# Flasher_2Ch_Astable.net
KiCad netlist of a schematic drawn in Altium Designer
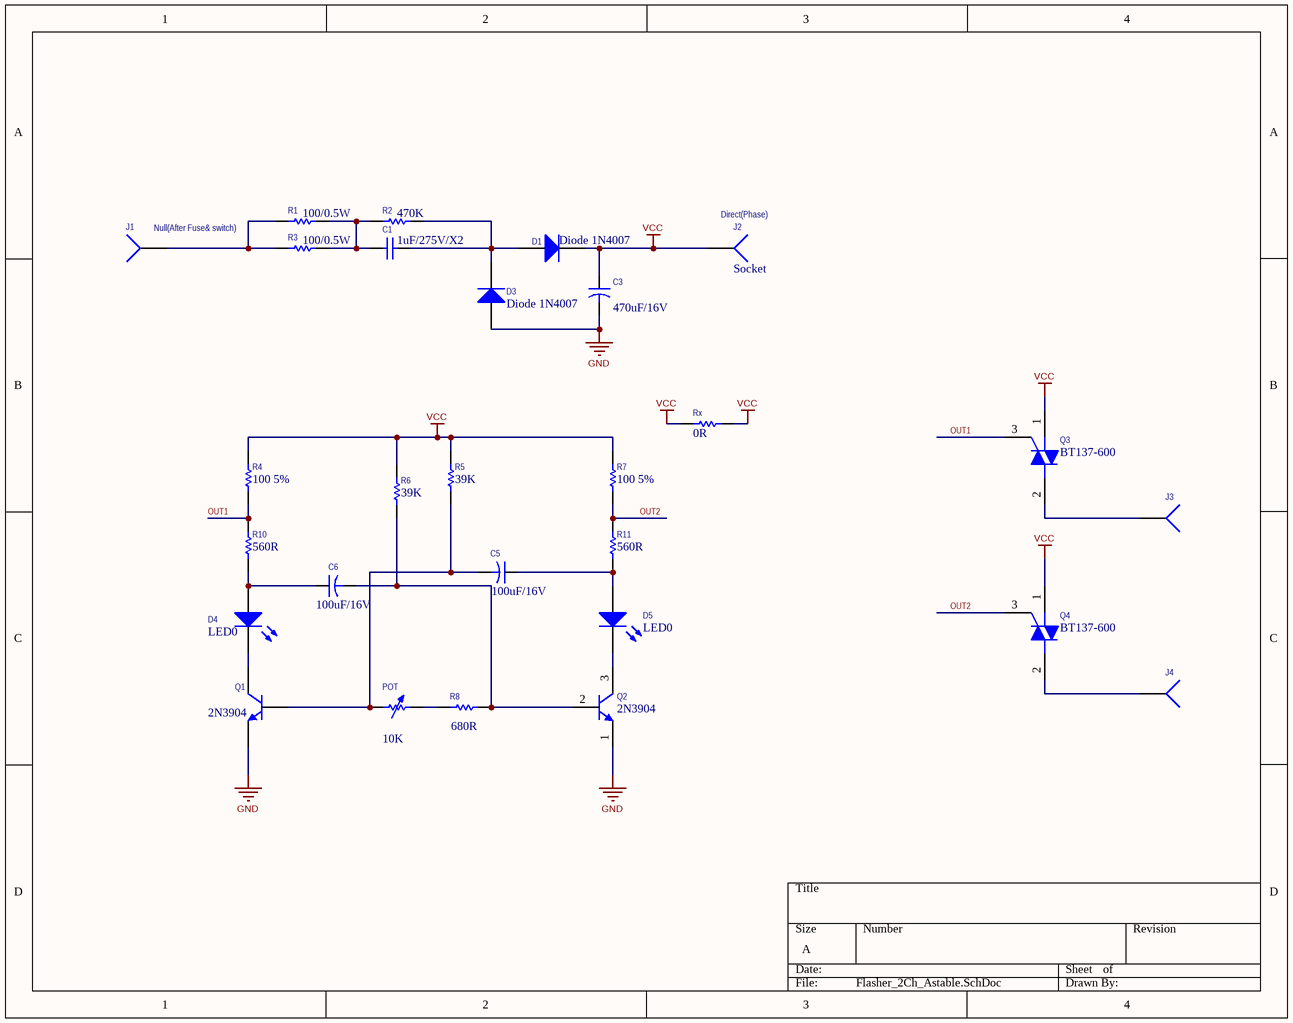
[diagram p0: Flasher_2Ch_Astable.SchDoc]

(export (version "E")
  (design (tool "Eeschema 10.0.6"))
  (components
    (comp (ref "C1")
      (value "1uF/275V/X2")
      (footprint "Cap_polyester_275V_P22.5")
      (description "Capacitor")
      (fields (field (name "Comment") "Cap") (field (name "PUBLISHER") "Altium Limited"))
      (libsource (lib "Miscellaneous Devices") (part "Cap"))
    )
    (comp (ref "C3")
      (value "470uF/16V")
      (footprint "Cap electrolitic radial 8x12-3.5")
      (description "Capacitor")
      (fields (field (name "Comment") "Cap2") (field (name "PUBLISHER") "Altium Limited"))
      (libsource (lib "Miscellaneous Devices") (part "Cap2"))
    )
    (comp (ref "C5")
      (value "100uF/16V")
      (footprint "Cap electrolitic radial 5x11-2")
      (description "Capacitor")
      (fields (field (name "Comment") "Cap2") (field (name "PUBLISHER") "Altium Limited"))
      (libsource (lib "Miscellaneous Devices") (part "Cap2"))
    )
    (comp (ref "C6")
      (value "100uF/16V")
      (footprint "Cap electrolitic radial 5x11-2")
      (description "Capacitor")
      (fields (field (name "Comment") "Cap2") (field (name "PUBLISHER") "Altium Limited"))
      (libsource (lib "Miscellaneous Devices") (part "Cap2"))
    )
    (comp (ref "D1")
      (value "Diode 1N4007")
      (footprint "DO-204AL")
      (description "1 Amp General Purpose Rectifier")
      (fields (field (name "PUBLISHER") "Altium Limited"))
      (libsource (lib "Miscellaneous Devices") (part "Diode 1N4007"))
    )
    (comp (ref "D3")
      (value "Diode 1N4007")
      (footprint "DO-204AL")
      (description "1 Amp General Purpose Rectifier")
      (fields (field (name "PUBLISHER") "Altium Limited"))
      (libsource (lib "Miscellaneous Devices") (part "Diode 1N4007"))
    )
    (comp (ref "D4")
      (value "LED0")
      (footprint "LED5MM_RED")
      (description "Typical INFRARED GaAs LED")
      (fields (field (name "PUBLISHER") "Altium Limited"))
      (libsource (lib "Miscellaneous Devices") (part "LED0"))
    )
    (comp (ref "D5")
      (value "LED0")
      (footprint "LED5MM_RED")
      (description "Typical INFRARED GaAs LED")
      (fields (field (name "PUBLISHER") "Altium Limited"))
      (libsource (lib "Miscellaneous Devices") (part "LED0"))
    )
    (comp (ref "J1")
      (value "Socket")
      (footprint "PIN1")
      (fields (field (name "PUBLISHER") "Altium Limited"))
      (libsource (lib "Miscellaneous Connectors") (part "Socket"))
    )
    (comp (ref "J2")
      (value "Socket")
      (footprint "PIN1")
      (fields (field (name "PUBLISHER") "Altium Limited"))
      (libsource (lib "Miscellaneous Connectors") (part "Socket"))
    )
    (comp (ref "J3")
      (value "Socket")
      (footprint "PIN1")
      (fields (field (name "PUBLISHER") "Altium Limited"))
      (libsource (lib "Miscellaneous Connectors") (part "Socket"))
    )
    (comp (ref "J4")
      (value "Socket")
      (footprint "PIN1")
      (fields (field (name "PUBLISHER") "Altium Limited"))
      (libsource (lib "Miscellaneous Connectors") (part "Socket"))
    )
    (comp (ref "POT")
      (value "10K")
      (footprint "AXIAL-0.4")
      (description "Variable Resistor")
      (fields (field (name "Comment") "Res Adj1") (field (name "PUBLISHER") "Altium Limited"))
      (libsource (lib "Miscellaneous Devices") (part "Res Adj1"))
    )
    (comp (ref "Q1")
      (value "2N3904")
      (footprint "TO-92 CF REV")
      (description "NPN General Purpose Amplifier")
      (fields (field (name "PUBLISHER") "Altium Limited"))
      (libsource (lib "Miscellaneous Devices") (part "2N3904"))
    )
    (comp (ref "Q2")
      (value "2N3904")
      (footprint "TO-92 CF")
      (description "NPN General Purpose Amplifier")
      (fields (field (name "PUBLISHER") "Altium Limited"))
      (libsource (lib "") (part "2N3904_1"))
    )
    (comp (ref "Q3")
      (value "BT137-600")
      (footprint "TO-220 AB with heatsink ya25")
      (description "Silicon Bidirectional Triode Thyristor")
      (fields (field (name "PUBLISHER") "Altium Limited"))
      (libsource (lib "Miscellaneous Devices") (part "Triac"))
    )
    (comp (ref "Q4")
      (value "BT137-600")
      (footprint "TO-220 AB with heatsink ya25")
      (description "Silicon Bidirectional Triode Thyristor")
      (fields (field (name "PUBLISHER") "Altium Limited"))
      (libsource (lib "Miscellaneous Devices") (part "Triac"))
    )
    (comp (ref "R1")
      (value "100/0.5W")
      (footprint "Axial 0_5W 5_0mm")
      (description "Resistor")
      (fields (field (name "Comment") "Res1") (field (name "PUBLISHER") "Altium Limited"))
      (libsource (lib "Miscellaneous Devices") (part "Res1"))
    )
    (comp (ref "R2")
      (value "470K")
      (footprint "Axial 0_25 W, 0_4 IN LEAD PITCH")
      (description "Resistor")
      (fields (field (name "Comment") "Res1") (field (name "PUBLISHER") "Altium Limited"))
      (libsource (lib "Miscellaneous Devices") (part "Res1"))
    )
    (comp (ref "R3")
      (value "100/0.5W")
      (footprint "Axial 0_5W 5_0mm")
      (description "Resistor")
      (fields (field (name "Comment") "Res1") (field (name "PUBLISHER") "Altium Limited"))
      (libsource (lib "Miscellaneous Devices") (part "Res1"))
    )
    (comp (ref "R4")
      (value "100 5%")
      (footprint "Axial 0_25 W, 0_4 IN LEAD PITCH")
      (description "Resistor")
      (fields (field (name "Comment") "Res1") (field (name "PUBLISHER") "Altium Limited"))
      (libsource (lib "Miscellaneous Devices") (part "Res1"))
    )
    (comp (ref "R5")
      (value "39K")
      (footprint "Axial 0_25 W, 0_4 IN LEAD PITCH")
      (description "Resistor")
      (fields (field (name "Comment") "Res1") (field (name "PUBLISHER") "Altium Limited"))
      (libsource (lib "Miscellaneous Devices") (part "Res1"))
    )
    (comp (ref "R6")
      (value "39K")
      (footprint "Axial 0_25 W, 0_4 IN LEAD PITCH")
      (description "Resistor")
      (fields (field (name "Comment") "Res1") (field (name "PUBLISHER") "Altium Limited"))
      (libsource (lib "Miscellaneous Devices") (part "Res1"))
    )
    (comp (ref "R7")
      (value "100 5%")
      (footprint "Axial 0_25 W, 0_4 IN LEAD PITCH")
      (description "Resistor")
      (fields (field (name "Comment") "Res1") (field (name "PUBLISHER") "Altium Limited"))
      (libsource (lib "Miscellaneous Devices") (part "Res1"))
    )
    (comp (ref "R8")
      (value "680R")
      (footprint "Axial 0_25 W, 0_4 IN LEAD PITCH")
      (description "Resistor")
      (fields (field (name "Comment") "Res1") (field (name "PUBLISHER") "Altium Limited"))
      (libsource (lib "Miscellaneous Devices") (part "Res1"))
    )
    (comp (ref "R10")
      (value "560R")
      (footprint "Axial 0_25 W, 0_4 IN LEAD PITCH")
      (description "Resistor")
      (fields (field (name "Comment") "Res1") (field (name "PUBLISHER") "Altium Limited"))
      (libsource (lib "Miscellaneous Devices") (part "Res1"))
    )
    (comp (ref "R11")
      (value "560R")
      (footprint "Axial 0_25 W, 0_4 IN LEAD PITCH")
      (description "Resistor")
      (fields (field (name "Comment") "Res1") (field (name "PUBLISHER") "Altium Limited"))
      (libsource (lib "Miscellaneous Devices") (part "Res1"))
    )
    (comp (ref "Rx")
      (value "0R")
      (footprint "axial-0.4")
      (description "Resistor")
      (fields (field (name "Comment") "Res1") (field (name "PUBLISHER") "Altium Limited"))
      (libsource (lib "Miscellaneous Devices") (part "Res1"))
    )
  )
  (nets
    (net (code "1") (name "/OUT1") (class "Default")
      (node (ref "Q3") (pin "3") (pinfunction "G_3") (pintype "passive"))
      (node (ref "R10") (pin "2") (pinfunction "2_2") (pintype "passive"))
      (node (ref "R4") (pin "1") (pinfunction "1_1") (pintype "passive"))
    )
    (net (code "2") (name "/OUT2") (class "Default")
      (node (ref "Q4") (pin "3") (pinfunction "G_3") (pintype "passive"))
      (node (ref "R11") (pin "2") (pinfunction "2_2") (pintype "passive"))
      (node (ref "R7") (pin "1") (pinfunction "1_1") (pintype "passive"))
    )
    (net (code "3") (name "GND") (class "Default")
      (node (ref "C3") (pin "2") (pinfunction "2_2") (pintype "passive"))
      (node (ref "D3") (pin "1") (pinfunction "A_1") (pintype "passive"))
      (node (ref "Q1") (pin "1") (pinfunction "E_1") (pintype "passive"))
      (node (ref "Q2") (pin "1") (pinfunction "E_1") (pintype "passive"))
    )
    (net (code "4") (name "Net-(C1-Pad1)") (class "Default")
      (node (ref "C1") (pin "1") (pinfunction "1_1") (pintype "passive"))
      (node (ref "R1") (pin "2") (pinfunction "2_2") (pintype "passive"))
      (node (ref "R2") (pin "1") (pinfunction "1_1") (pintype "passive"))
      (node (ref "R3") (pin "2") (pinfunction "2_2") (pintype "passive"))
    )
    (net (code "5") (name "Net-(D1-A)") (class "Default")
      (node (ref "C1") (pin "2") (pinfunction "2_2") (pintype "passive"))
      (node (ref "D1") (pin "1") (pinfunction "A_1") (pintype "passive"))
      (node (ref "D3") (pin "2") (pinfunction "K_2") (pintype "passive"))
      (node (ref "R2") (pin "2") (pinfunction "2_2") (pintype "passive"))
    )
    (net (code "6") (name "Net-(D4-A)") (class "Default")
      (node (ref "C6") (pin "1") (pinfunction "1_1") (pintype "passive"))
      (node (ref "D4") (pin "1") (pinfunction "A_1") (pintype "passive"))
      (node (ref "R10") (pin "1") (pinfunction "1_1") (pintype "passive"))
    )
    (net (code "7") (name "Net-(D4-K)") (class "Default")
      (node (ref "D4") (pin "2") (pinfunction "K_2") (pintype "passive"))
      (node (ref "Q1") (pin "3") (pinfunction "C_3") (pintype "passive"))
    )
    (net (code "8") (name "Net-(D5-A)") (class "Default")
      (node (ref "C5") (pin "1") (pinfunction "1_1") (pintype "passive"))
      (node (ref "D5") (pin "1") (pinfunction "A_1") (pintype "passive"))
      (node (ref "R11") (pin "1") (pinfunction "1_1") (pintype "passive"))
    )
    (net (code "9") (name "Net-(D5-K)") (class "Default")
      (node (ref "D5") (pin "2") (pinfunction "K_2") (pintype "passive"))
      (node (ref "Q2") (pin "3") (pinfunction "C_3") (pintype "passive"))
    )
    (net (code "10") (name "Net-(J1-Pad1)") (class "Default")
      (node (ref "J1") (pin "1") (pinfunction "1_1") (pintype "passive"))
      (node (ref "R1") (pin "1") (pinfunction "1_1") (pintype "passive"))
      (node (ref "R3") (pin "1") (pinfunction "1_1") (pintype "passive"))
    )
    (net (code "11") (name "Net-(POT-Pad2)") (class "Default")
      (node (ref "POT") (pin "2") (pinfunction "2_2") (pintype "passive"))
      (node (ref "R8") (pin "2") (pinfunction "2_2") (pintype "passive"))
    )
    (net (code "12") (name "Net-(Q1-B)") (class "Default")
      (node (ref "C5") (pin "2") (pinfunction "2_2") (pintype "passive"))
      (node (ref "POT") (pin "1") (pinfunction "1_1") (pintype "passive"))
      (node (ref "Q1") (pin "2") (pinfunction "B_2") (pintype "passive"))
      (node (ref "R5") (pin "1") (pinfunction "1_1") (pintype "passive"))
    )
    (net (code "13") (name "Net-(Q2-B)") (class "Default")
      (node (ref "C6") (pin "2") (pinfunction "2_2") (pintype "passive"))
      (node (ref "Q2") (pin "2") (pinfunction "B_2") (pintype "passive"))
      (node (ref "R6") (pin "1") (pinfunction "1_1") (pintype "passive"))
      (node (ref "R8") (pin "1") (pinfunction "1_1") (pintype "passive"))
    )
    (net (code "14") (name "Net-(Q3-M2)") (class "Default")
      (node (ref "J3") (pin "1") (pinfunction "1_1") (pintype "passive"))
      (node (ref "Q3") (pin "2") (pinfunction "M2_2") (pintype "passive"))
    )
    (net (code "15") (name "Net-(Q4-M2)") (class "Default")
      (node (ref "J4") (pin "1") (pinfunction "1_1") (pintype "passive"))
      (node (ref "Q4") (pin "2") (pinfunction "M2_2") (pintype "passive"))
    )
    (net (code "16") (name "VCC") (class "Default")
      (node (ref "C3") (pin "1") (pinfunction "1_1") (pintype "passive"))
      (node (ref "D1") (pin "2") (pinfunction "K_2") (pintype "passive"))
      (node (ref "J2") (pin "1") (pinfunction "1_1") (pintype "passive"))
      (node (ref "Q3") (pin "1") (pinfunction "M1_1") (pintype "passive"))
      (node (ref "Q4") (pin "1") (pinfunction "M1_1") (pintype "passive"))
      (node (ref "R4") (pin "2") (pinfunction "2_2") (pintype "passive"))
      (node (ref "R5") (pin "2") (pinfunction "2_2") (pintype "passive"))
      (node (ref "R6") (pin "2") (pinfunction "2_2") (pintype "passive"))
      (node (ref "R7") (pin "2") (pinfunction "2_2") (pintype "passive"))
      (node (ref "Rx") (pin "1") (pinfunction "1_1") (pintype "passive"))
      (node (ref "Rx") (pin "2") (pinfunction "2_2") (pintype "passive"))
    )
  )
)
